# pomppurobotti.net
KiCad netlist of a schematic drawn in EAGLE
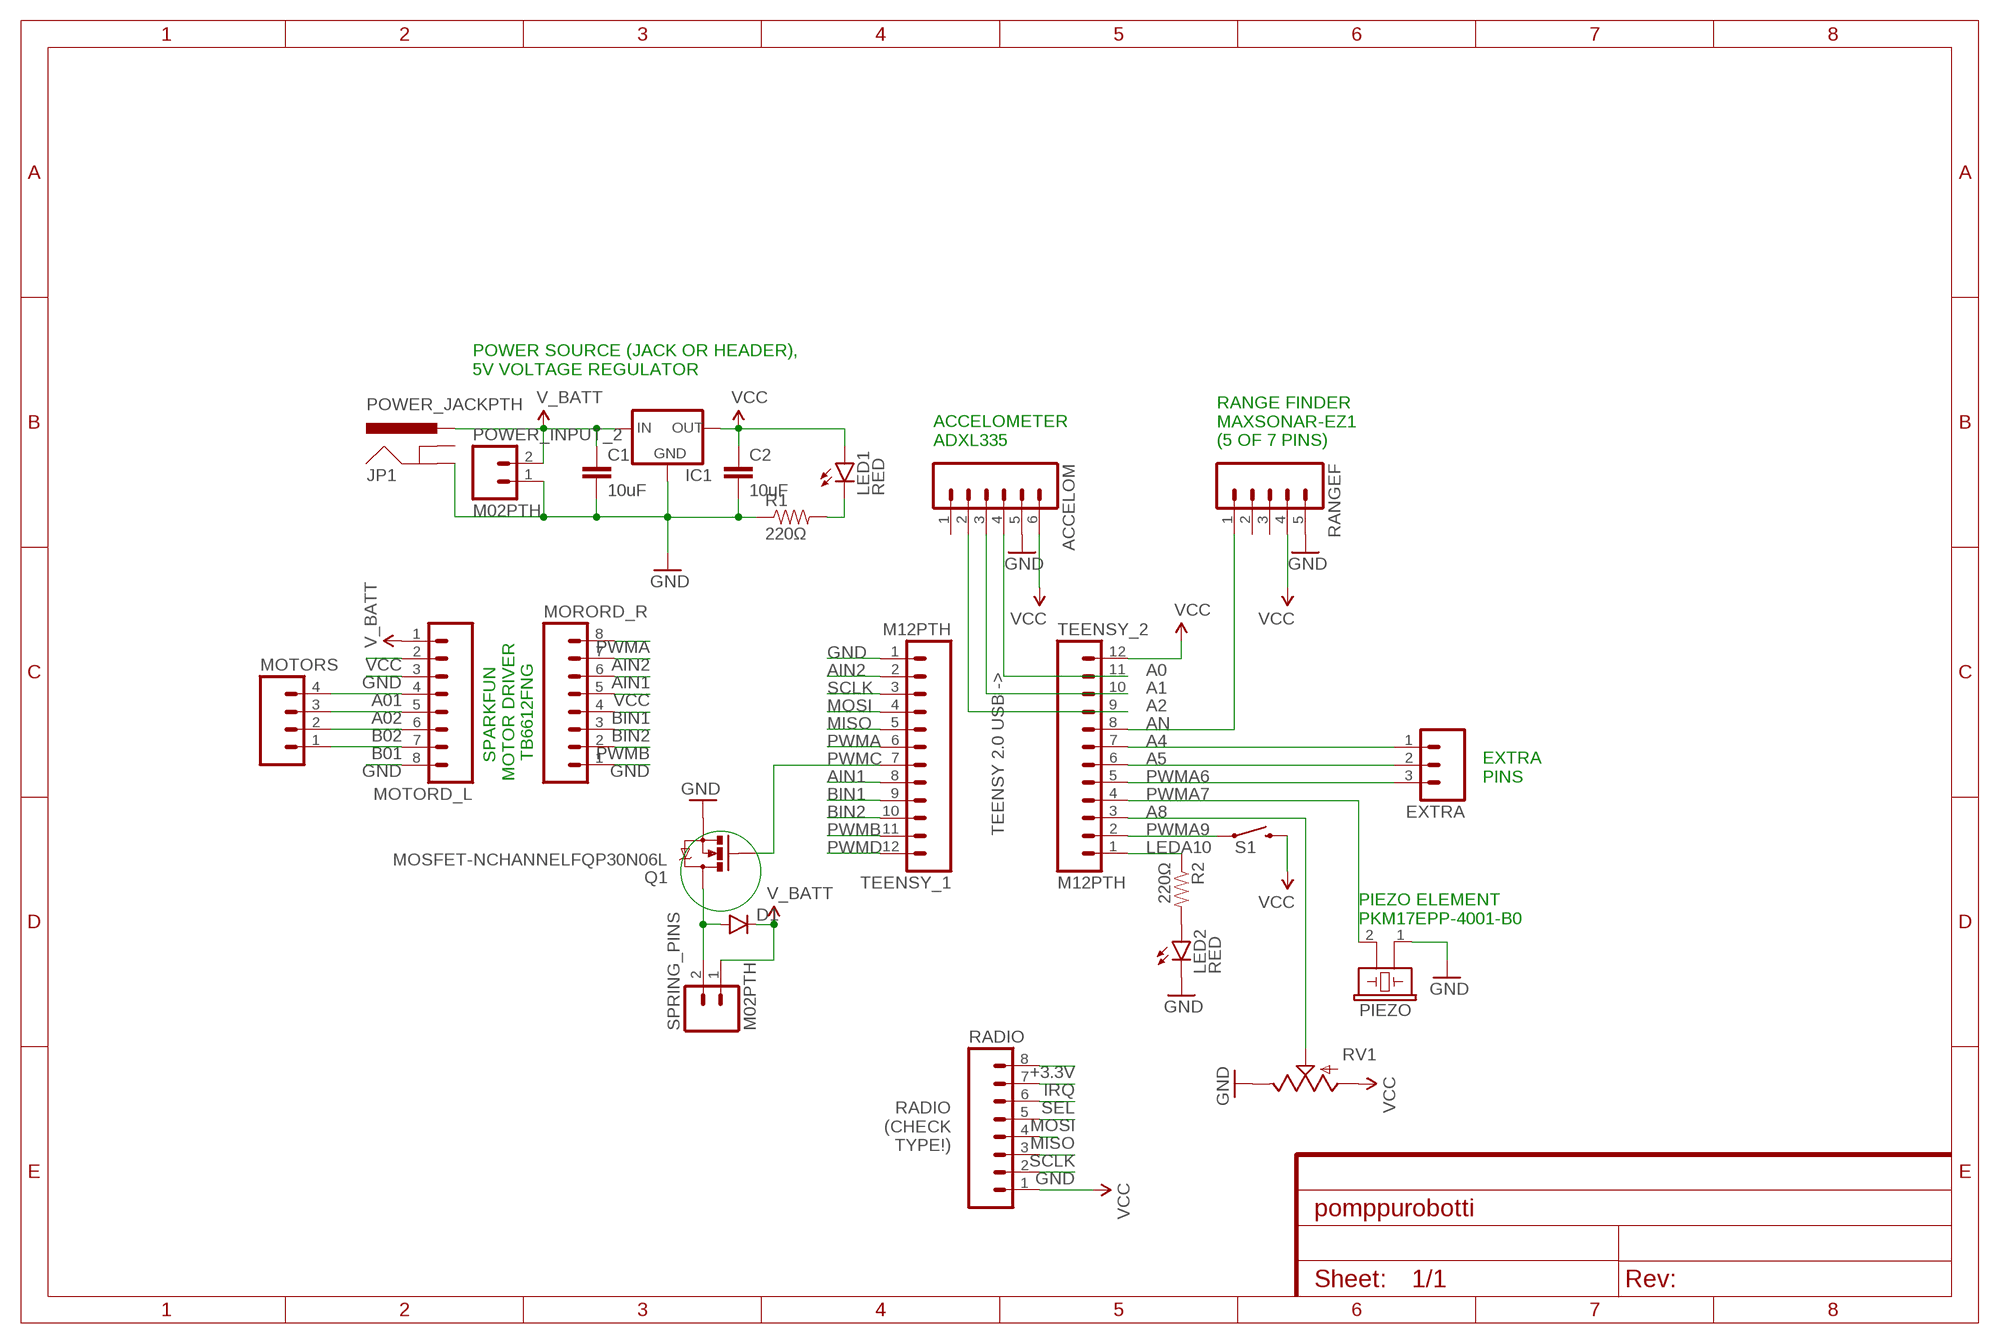
[diagram p0: schematic, sheet 1]

(export (version "E")
  (design (tool "Eeschema 10.0.6"))
  (components
    (comp (ref "ACCELOM")
      (value "M06SILK_FEMALE_PTH")
      (footprint "eagle-import:1X06")
      (libsource (lib "eagle-import") (part "M06SILK_FEMALE_PTH"))
    )
    (comp (ref "C1")
      (value "10uF")
      (footprint "eagle-import:CAP-PTH-SMALL")
      (libsource (lib "eagle-import") (part "CAPPTH"))
    )
    (comp (ref "C2")
      (value "10uF")
      (footprint "eagle-import:CAP-PTH-SMALL")
      (libsource (lib "eagle-import") (part "CAPPTH"))
    )
    (comp (ref "D1")
      (value "DIODEPTH")
      (footprint "eagle-import:DIODE-1N4001")
      (libsource (lib "eagle-import") (part "DIODEPTH"))
    )
    (comp (ref "EXTRA")
      (value "M03PTH")
      (footprint "eagle-import:1X03")
      (libsource (lib "eagle-import") (part "M03PTH"))
    )
    (comp (ref "IC1")
      (value "V_REG_78XX-TO-220")
      (footprint "eagle-import:TO-220-ALT")
      (libsource (lib "eagle-import") (part "V_REG_78XX-TO-220"))
    )
    (comp (ref "JP1")
      (value "POWER_JACKPTH")
      (footprint "eagle-import:POWER_JACK_PTH")
      (libsource (lib "eagle-import") (part "POWER_JACKPTH"))
    )
    (comp (ref "LED1")
      (value "RED")
      (footprint "eagle-import:LED5MM")
      (libsource (lib "eagle-import") (part "LED5MM"))
    )
    (comp (ref "LED2")
      (value "RED")
      (footprint "eagle-import:LED5MM")
      (libsource (lib "eagle-import") (part "LED5MM"))
    )
    (comp (ref "MORORD_R")
      (value "M08LONGPADS")
      (footprint "eagle-import:1X08_LONGPADS")
      (libsource (lib "eagle-import") (part "M08LONGPADS"))
    )
    (comp (ref "MOTORD_L")
      (value "M08LONGPADS")
      (footprint "eagle-import:1X08_LONGPADS")
      (libsource (lib "eagle-import") (part "M08LONGPADS"))
    )
    (comp (ref "MOTORS")
      (value "M04PTH")
      (footprint "eagle-import:1X04")
      (libsource (lib "eagle-import") (part "M04PTH"))
    )
    (comp (ref "PIEZO")
      (value "EFBAA40D101")
      (footprint "eagle-import:EFBAA40D101")
      (libsource (lib "eagle-import") (part "EFB?AA40D101"))
    )
    (comp (ref "POWER_INPUT_2")
      (value "M02PTH")
      (footprint "eagle-import:1X02")
      (libsource (lib "eagle-import") (part "M02PTH"))
    )
    (comp (ref "Q1")
      (value "MOSFET-NCHANNELFQP30N06L")
      (footprint "eagle-import:TO220V")
      (libsource (lib "eagle-import") (part "MOSFET-NCHANNELFQP30N06L"))
    )
    (comp (ref "R1")
      (value "220Ω")
      (footprint "eagle-import:AXIAL-0.3")
      (libsource (lib "eagle-import") (part "RESISTORAXIAL-0.3"))
    )
    (comp (ref "R2")
      (value "220Ω")
      (footprint "eagle-import:AXIAL-0.3")
      (libsource (lib "eagle-import") (part "RESISTORAXIAL-0.3"))
    )
    (comp (ref "RADIO")
      (value "M08")
      (footprint "eagle-import:1X08_ROUND")
      (libsource (lib "eagle-import") (part "M08"))
    )
    (comp (ref "RANGEF")
      (value "M05PTH")
      (footprint "eagle-import:1X05")
      (libsource (lib "eagle-import") (part "M05PTH"))
    )
    (comp (ref "RV1")
      (value "POTTRIM")
      (footprint "eagle-import:TRIM_POT")
      (libsource (lib "eagle-import") (part "POTTRIM"))
    )
    (comp (ref "S1")
      (value "SWITCH-MOMENTARY-2PTH")
      (footprint "eagle-import:TACTILE-PTH")
      (libsource (lib "eagle-import") (part "SWITCH-MOMENTARY-2PTH"))
    )
    (comp (ref "SPRING_PINS")
      (value "M02PTH")
      (footprint "eagle-import:1X02")
      (libsource (lib "eagle-import") (part "M02PTH"))
    )
    (comp (ref "TEENSY_1")
      (value "M12PTH")
      (footprint "eagle-import:1X12")
      (libsource (lib "eagle-import") (part "M12PTH"))
    )
    (comp (ref "TEENSY_2")
      (value "M12PTH")
      (footprint "eagle-import:1X12")
      (libsource (lib "eagle-import") (part "M12PTH"))
    )
  )
  (nets
    (net (code "1") (name "/+3.3V") (class "Default")
      (node (ref "RADIO") (pin "8") (pinfunction "8_8") (pintype "passive"))
    )
    (net (code "2") (name "/A0") (class "Default")
      (node (ref "ACCELOM") (pin "2") (pinfunction "2_2") (pintype "passive"))
      (node (ref "TEENSY_2") (pin "9") (pinfunction "9_9") (pintype "passive"))
    )
    (net (code "3") (name "/A01") (class "Default")
      (node (ref "MOTORD_L") (pin "4") (pinfunction "4_4") (pintype "passive"))
      (node (ref "MOTORS") (pin "4") (pinfunction "4_4") (pintype "passive"))
    )
    (net (code "4") (name "/A1") (class "Default")
      (node (ref "ACCELOM") (pin "3") (pinfunction "3_3") (pintype "passive"))
      (node (ref "TEENSY_2") (pin "10") (pinfunction "10_10") (pintype "passive"))
    )
    (net (code "5") (name "/A2") (class "Default")
      (node (ref "ACCELOM") (pin "4") (pinfunction "4_4") (pintype "passive"))
      (node (ref "TEENSY_2") (pin "11") (pinfunction "11_11") (pintype "passive"))
    )
    (net (code "6") (name "/A02") (class "Default")
      (node (ref "MOTORD_L") (pin "5") (pinfunction "5_5") (pintype "passive"))
      (node (ref "MOTORS") (pin "3") (pinfunction "3_3") (pintype "passive"))
    )
    (net (code "7") (name "/A4") (class "Default")
      (node (ref "EXTRA") (pin "1") (pinfunction "1_1") (pintype "passive"))
      (node (ref "TEENSY_2") (pin "7") (pinfunction "7_7") (pintype "passive"))
    )
    (net (code "8") (name "/A5") (class "Default")
      (node (ref "EXTRA") (pin "2") (pinfunction "2_2") (pintype "passive"))
      (node (ref "TEENSY_2") (pin "6") (pinfunction "6_6") (pintype "passive"))
    )
    (net (code "9") (name "/A8") (class "Default")
      (node (ref "RV1") (pin "1") (pinfunction "S_1") (pintype "passive"))
      (node (ref "TEENSY_2") (pin "3") (pinfunction "3_3") (pintype "passive"))
    )
    (net (code "10") (name "/AIN1") (class "Default")
      (node (ref "MORORD_R") (pin "6") (pinfunction "6_6") (pintype "passive"))
      (node (ref "TEENSY_1") (pin "8") (pinfunction "8_8") (pintype "passive"))
    )
    (net (code "11") (name "/AIN2") (class "Default")
      (node (ref "MORORD_R") (pin "7") (pinfunction "7_7") (pintype "passive"))
      (node (ref "TEENSY_1") (pin "2") (pinfunction "2_2") (pintype "passive"))
    )
    (net (code "12") (name "/AN") (class "Default")
      (node (ref "RANGEF") (pin "1") (pinfunction "1_1") (pintype "passive"))
      (node (ref "TEENSY_2") (pin "8") (pinfunction "8_8") (pintype "passive"))
    )
    (net (code "13") (name "/B01") (class "Default")
      (node (ref "MOTORD_L") (pin "7") (pinfunction "7_7") (pintype "passive"))
      (node (ref "MOTORS") (pin "1") (pinfunction "1_1") (pintype "passive"))
    )
    (net (code "14") (name "/B02") (class "Default")
      (node (ref "MOTORD_L") (pin "6") (pinfunction "6_6") (pintype "passive"))
      (node (ref "MOTORS") (pin "2") (pinfunction "2_2") (pintype "passive"))
    )
    (net (code "15") (name "/BIN1") (class "Default")
      (node (ref "MORORD_R") (pin "4") (pinfunction "4_4") (pintype "passive"))
      (node (ref "TEENSY_1") (pin "9") (pinfunction "9_9") (pintype "passive"))
    )
    (net (code "16") (name "/BIN2") (class "Default")
      (node (ref "MORORD_R") (pin "3") (pinfunction "3_3") (pintype "passive"))
      (node (ref "TEENSY_1") (pin "10") (pinfunction "10_10") (pintype "passive"))
    )
    (net (code "17") (name "/IRQ") (class "Default")
      (node (ref "RADIO") (pin "7") (pinfunction "7_7") (pintype "passive"))
    )
    (net (code "18") (name "/LEDA10") (class "Default")
      (node (ref "R2") (pin "P$1") (pinfunction "1_P$1") (pintype "passive"))
      (node (ref "TEENSY_2") (pin "1") (pinfunction "1_1") (pintype "passive"))
    )
    (net (code "19") (name "/MISO") (class "Default")
      (node (ref "RADIO") (pin "4") (pinfunction "4_4") (pintype "passive"))
      (node (ref "TEENSY_1") (pin "5") (pinfunction "5_5") (pintype "passive"))
    )
    (net (code "20") (name "/MOSI") (class "Default")
      (node (ref "RADIO") (pin "5") (pinfunction "5_5") (pintype "passive"))
      (node (ref "TEENSY_1") (pin "4") (pinfunction "4_4") (pintype "passive"))
    )
    (net (code "21") (name "/PWMA") (class "Default")
      (node (ref "MORORD_R") (pin "8") (pinfunction "8_8") (pintype "passive"))
      (node (ref "TEENSY_1") (pin "6") (pinfunction "6_6") (pintype "passive"))
    )
    (net (code "22") (name "/PWMA6") (class "Default")
      (node (ref "EXTRA") (pin "3") (pinfunction "3_3") (pintype "passive"))
      (node (ref "TEENSY_2") (pin "5") (pinfunction "5_5") (pintype "passive"))
    )
    (net (code "23") (name "/PWMA7") (class "Default")
      (node (ref "PIEZO") (pin "2") (pinfunction "2_2") (pintype "passive"))
      (node (ref "TEENSY_2") (pin "4") (pinfunction "4_4") (pintype "passive"))
    )
    (net (code "24") (name "/PWMA9") (class "Default")
      (node (ref "S1") (pin "1") (pinfunction "1_1") (pintype "passive"))
      (node (ref "TEENSY_2") (pin "2") (pinfunction "2_2") (pintype "passive"))
    )
    (net (code "25") (name "/PWMB") (class "Default")
      (node (ref "MORORD_R") (pin "2") (pinfunction "2_2") (pintype "passive"))
      (node (ref "TEENSY_1") (pin "11") (pinfunction "11_11") (pintype "passive"))
    )
    (net (code "26") (name "/PWMC") (class "Default")
      (node (ref "Q1") (pin "1") (pinfunction "G_1") (pintype "passive"))
      (node (ref "TEENSY_1") (pin "7") (pinfunction "7_7") (pintype "passive"))
    )
    (net (code "27") (name "/PWMD") (class "Default")
      (node (ref "TEENSY_1") (pin "12") (pinfunction "12_12") (pintype "passive"))
    )
    (net (code "28") (name "/SCLK") (class "Default")
      (node (ref "RADIO") (pin "3") (pinfunction "3_3") (pintype "passive"))
      (node (ref "TEENSY_1") (pin "3") (pinfunction "3_3") (pintype "passive"))
    )
    (net (code "29") (name "/SEL") (class "Default")
      (node (ref "RADIO") (pin "6") (pinfunction "6_6") (pintype "passive"))
    )
    (net (code "30") (name "GND") (class "Default")
      (node (ref "ACCELOM") (pin "5") (pinfunction "5_5") (pintype "passive"))
      (node (ref "C1") (pin "2") (pinfunction "2_2") (pintype "passive"))
      (node (ref "C2") (pin "2") (pinfunction "2_2") (pintype "passive"))
      (node (ref "IC1") (pin "GND") (pinfunction "GND_GND") (pintype "input"))
      (node (ref "JP1") (pin "GND") (pinfunction "GND_GND") (pintype "bidirectional"))
      (node (ref "LED2") (pin "K") (pinfunction "C_K") (pintype "passive"))
      (node (ref "MORORD_R") (pin "1") (pinfunction "1_1") (pintype "passive"))
      (node (ref "MOTORD_L") (pin "3") (pinfunction "3_3") (pintype "passive"))
      (node (ref "MOTORD_L") (pin "8") (pinfunction "8_8") (pintype "passive"))
      (node (ref "PIEZO") (pin "1") (pinfunction "1_1") (pintype "passive"))
      (node (ref "POWER_INPUT_2") (pin "1") (pinfunction "1_1") (pintype "passive"))
      (node (ref "Q1") (pin "3") (pinfunction "S_3") (pintype "passive"))
      (node (ref "R1") (pin "P$1") (pinfunction "1_P$1") (pintype "passive"))
      (node (ref "RADIO") (pin "2") (pinfunction "2_2") (pintype "passive"))
      (node (ref "RANGEF") (pin "5") (pinfunction "5_5") (pintype "passive"))
      (node (ref "RV1") (pin "2") (pinfunction "E_2") (pintype "passive"))
      (node (ref "TEENSY_1") (pin "1") (pinfunction "1_1") (pintype "passive"))
    )
    (net (code "31") (name "Net-(LED1-C)") (class "Default")
      (node (ref "LED1") (pin "K") (pinfunction "C_K") (pintype "passive"))
      (node (ref "R1") (pin "P$2") (pinfunction "2_P$2") (pintype "passive"))
    )
    (net (code "32") (name "Net-(Q1-D)") (class "Default")
      (node (ref "D1") (pin "A") (pinfunction "A_A") (pintype "passive"))
      (node (ref "Q1") (pin "2") (pinfunction "D_2") (pintype "passive"))
      (node (ref "SPRING_PINS") (pin "2") (pinfunction "2_2") (pintype "passive"))
    )
    (net (code "33") (name "Net-(R2-2)") (class "Default")
      (node (ref "LED2") (pin "A") (pinfunction "A_A") (pintype "passive"))
      (node (ref "R2") (pin "P$2") (pinfunction "2_P$2") (pintype "passive"))
    )
    (net (code "34") (name "VCC") (class "Default")
      (node (ref "ACCELOM") (pin "6") (pinfunction "6_6") (pintype "passive"))
      (node (ref "C2") (pin "1") (pinfunction "1_1") (pintype "passive"))
      (node (ref "IC1") (pin "OUT") (pinfunction "OUT_OUT") (pintype "output"))
      (node (ref "LED1") (pin "A") (pinfunction "A_A") (pintype "passive"))
      (node (ref "MORORD_R") (pin "5") (pinfunction "5_5") (pintype "passive"))
      (node (ref "MOTORD_L") (pin "2") (pinfunction "2_2") (pintype "passive"))
      (node (ref "RADIO") (pin "1") (pinfunction "1_1") (pintype "passive"))
      (node (ref "RANGEF") (pin "4") (pinfunction "4_4") (pintype "passive"))
      (node (ref "RV1") (pin "3") (pinfunction "A_3") (pintype "passive"))
      (node (ref "S1") (pin "3") (pinfunction "2_3") (pintype "passive"))
      (node (ref "TEENSY_2") (pin "12") (pinfunction "12_12") (pintype "passive"))
    )
    (net (code "35") (name "V_BATT") (class "Default")
      (node (ref "C1") (pin "1") (pinfunction "1_1") (pintype "passive"))
      (node (ref "D1") (pin "C") (pinfunction "C_C") (pintype "passive"))
      (node (ref "IC1") (pin "IN") (pinfunction "IN_IN") (pintype "input"))
      (node (ref "JP1") (pin "PWR") (pinfunction "PWR_PWR") (pintype "bidirectional"))
      (node (ref "MOTORD_L") (pin "1") (pinfunction "1_1") (pintype "passive"))
      (node (ref "POWER_INPUT_2") (pin "2") (pinfunction "2_2") (pintype "passive"))
      (node (ref "SPRING_PINS") (pin "1") (pinfunction "1_1") (pintype "passive"))
    )
    (net (code "36") (name "unconnected-(ACCELOM-Pad1)") (class "Default")
      (node (ref "ACCELOM") (pin "1") (pinfunction "1_1") (pintype "passive"))
    )
    (net (code "37") (name "unconnected-(JP1-PadGNDBREAK)") (class "Default")
      (node (ref "JP1") (pin "GNDBREAK") (pinfunction "GNDBREAK_GNDBREAK") (pintype "bidirectional"))
    )
    (net (code "38") (name "unconnected-(RANGEF-Pad2)") (class "Default")
      (node (ref "RANGEF") (pin "2") (pinfunction "2_2") (pintype "passive"))
    )
    (net (code "39") (name "unconnected-(RANGEF-Pad3)") (class "Default")
      (node (ref "RANGEF") (pin "3") (pinfunction "3_3") (pintype "passive"))
    )
  )
)
